# PCB2.net
KiCad netlist of a schematic drawn in EAGLE
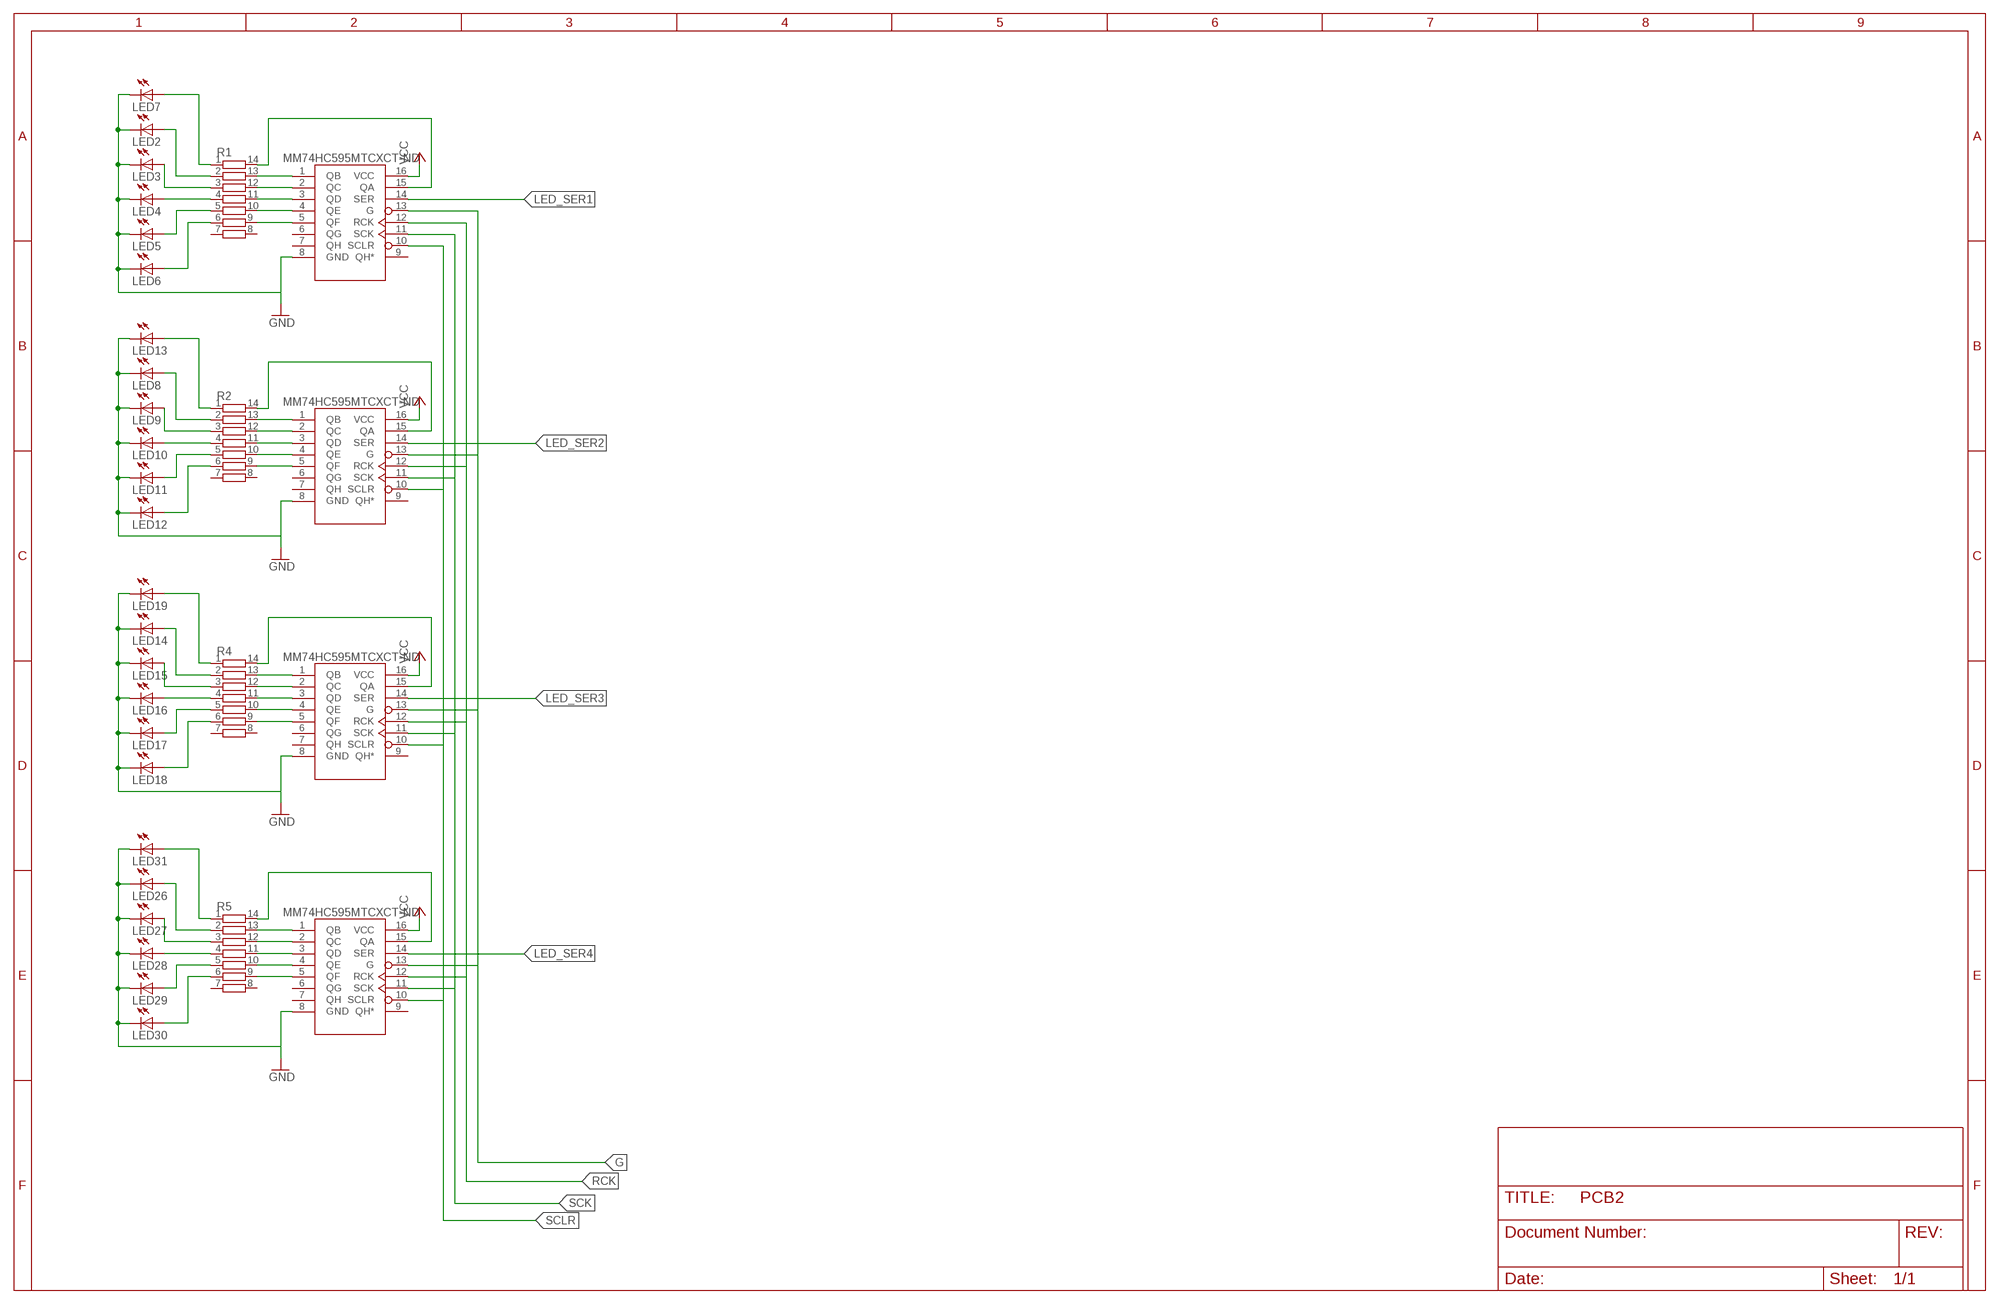
[diagram p0: schematic, sheet 1]

(export (version "E")
  (design (tool "Eeschema 10.0.6"))
  (components
    (comp (ref "LED2")
      (value "LEDSMT1206")
      (footprint "eagle-import:1206")
      (libsource (lib "eagle-import") (part "LEDSMT1206"))
    )
    (comp (ref "LED3")
      (value "LEDSMT1206")
      (footprint "eagle-import:1206")
      (libsource (lib "eagle-import") (part "LEDSMT1206"))
    )
    (comp (ref "LED4")
      (value "LEDSMT1206")
      (footprint "eagle-import:1206")
      (libsource (lib "eagle-import") (part "LEDSMT1206"))
    )
    (comp (ref "LED5")
      (value "LEDSMT1206")
      (footprint "eagle-import:1206")
      (libsource (lib "eagle-import") (part "LEDSMT1206"))
    )
    (comp (ref "LED6")
      (value "LEDSMT1206")
      (footprint "eagle-import:1206")
      (libsource (lib "eagle-import") (part "LEDSMT1206"))
    )
    (comp (ref "LED7")
      (value "LEDSMT1206")
      (footprint "eagle-import:1206")
      (libsource (lib "eagle-import") (part "LEDSMT1206"))
    )
    (comp (ref "LED8")
      (value "LEDSMT1206")
      (footprint "eagle-import:1206")
      (libsource (lib "eagle-import") (part "LEDSMT1206"))
    )
    (comp (ref "LED9")
      (value "LEDSMT1206")
      (footprint "eagle-import:1206")
      (libsource (lib "eagle-import") (part "LEDSMT1206"))
    )
    (comp (ref "LED10")
      (value "LEDSMT1206")
      (footprint "eagle-import:1206")
      (libsource (lib "eagle-import") (part "LEDSMT1206"))
    )
    (comp (ref "LED11")
      (value "LEDSMT1206")
      (footprint "eagle-import:1206")
      (libsource (lib "eagle-import") (part "LEDSMT1206"))
    )
    (comp (ref "LED12")
      (value "LEDSMT1206")
      (footprint "eagle-import:1206")
      (libsource (lib "eagle-import") (part "LEDSMT1206"))
    )
    (comp (ref "LED13")
      (value "LEDSMT1206")
      (footprint "eagle-import:1206")
      (libsource (lib "eagle-import") (part "LEDSMT1206"))
    )
    (comp (ref "LED14")
      (value "LEDSMT1206")
      (footprint "eagle-import:1206")
      (libsource (lib "eagle-import") (part "LEDSMT1206"))
    )
    (comp (ref "LED15")
      (value "LEDSMT1206")
      (footprint "eagle-import:1206")
      (libsource (lib "eagle-import") (part "LEDSMT1206"))
    )
    (comp (ref "LED16")
      (value "LEDSMT1206")
      (footprint "eagle-import:1206")
      (libsource (lib "eagle-import") (part "LEDSMT1206"))
    )
    (comp (ref "LED17")
      (value "LEDSMT1206")
      (footprint "eagle-import:1206")
      (libsource (lib "eagle-import") (part "LEDSMT1206"))
    )
    (comp (ref "LED18")
      (value "LEDSMT1206")
      (footprint "eagle-import:1206")
      (libsource (lib "eagle-import") (part "LEDSMT1206"))
    )
    (comp (ref "LED19")
      (value "LEDSMT1206")
      (footprint "eagle-import:1206")
      (libsource (lib "eagle-import") (part "LEDSMT1206"))
    )
    (comp (ref "LED26")
      (value "LEDSMT1206")
      (footprint "eagle-import:1206")
      (libsource (lib "eagle-import") (part "LEDSMT1206"))
    )
    (comp (ref "LED27")
      (value "LEDSMT1206")
      (footprint "eagle-import:1206")
      (libsource (lib "eagle-import") (part "LEDSMT1206"))
    )
    (comp (ref "LED28")
      (value "LEDSMT1206")
      (footprint "eagle-import:1206")
      (libsource (lib "eagle-import") (part "LEDSMT1206"))
    )
    (comp (ref "LED29")
      (value "LEDSMT1206")
      (footprint "eagle-import:1206")
      (libsource (lib "eagle-import") (part "LEDSMT1206"))
    )
    (comp (ref "LED30")
      (value "LEDSMT1206")
      (footprint "eagle-import:1206")
      (libsource (lib "eagle-import") (part "LEDSMT1206"))
    )
    (comp (ref "LED31")
      (value "LEDSMT1206")
      (footprint "eagle-import:1206")
      (libsource (lib "eagle-import") (part "LEDSMT1206"))
    )
    (comp (ref "R1")
      (value "4814P-T01")
      (footprint "eagle-import:4814P")
      (fields (field (name "MF") "BOURNS, INC.") (field (name "MPN") "4814P-T01-104LF"))
      (libsource (lib "eagle-import") (part "4814P-T01"))
    )
    (comp (ref "R2")
      (value "4814P-T01")
      (footprint "eagle-import:4814P")
      (fields (field (name "MF") "BOURNS, INC.") (field (name "MPN") "4814P-T01-104LF"))
      (libsource (lib "eagle-import") (part "4814P-T01"))
    )
    (comp (ref "R4")
      (value "4814P-T01")
      (footprint "eagle-import:4814P")
      (fields (field (name "MF") "BOURNS, INC.") (field (name "MPN") "4814P-T01-104LF"))
      (libsource (lib "eagle-import") (part "4814P-T01"))
    )
    (comp (ref "R5")
      (value "4814P-T01")
      (footprint "eagle-import:4814P")
      (fields (field (name "MF") "BOURNS, INC.") (field (name "MPN") "4814P-T01-104LF"))
      (libsource (lib "eagle-import") (part "4814P-T01"))
    )
    (comp (ref "U$1")
      (value "MM74HC595TSSOP-LD16")
      (footprint "eagle-import:MM74HC595MTCXCT-ND")
      (libsource (lib "eagle-import") (part "MM74HC595TSSOP-LD16"))
    )
    (comp (ref "U$3")
      (value "MM74HC595TSSOP-LD16")
      (footprint "eagle-import:MM74HC595MTCXCT-ND")
      (libsource (lib "eagle-import") (part "MM74HC595TSSOP-LD16"))
    )
    (comp (ref "U$4")
      (value "MM74HC595TSSOP-LD16")
      (footprint "eagle-import:MM74HC595MTCXCT-ND")
      (libsource (lib "eagle-import") (part "MM74HC595TSSOP-LD16"))
    )
    (comp (ref "U$5")
      (value "MM74HC595TSSOP-LD16")
      (footprint "eagle-import:MM74HC595MTCXCT-ND")
      (libsource (lib "eagle-import") (part "MM74HC595TSSOP-LD16"))
    )
  )
  (nets
    (net (code "1") (name "G") (class "Default")
      (node (ref "U$4") (pin "13") (pinfunction "G_13") (pintype "bidirectional"))
    )
    (net (code "2") (name "GND") (class "Default")
      (node (ref "LED10") (pin "C") (pinfunction "C_C") (pintype "passive"))
      (node (ref "LED11") (pin "C") (pinfunction "C_C") (pintype "passive"))
      (node (ref "LED12") (pin "C") (pinfunction "C_C") (pintype "passive"))
      (node (ref "LED13") (pin "C") (pinfunction "C_C") (pintype "passive"))
      (node (ref "LED14") (pin "C") (pinfunction "C_C") (pintype "passive"))
      (node (ref "LED15") (pin "C") (pinfunction "C_C") (pintype "passive"))
      (node (ref "LED16") (pin "C") (pinfunction "C_C") (pintype "passive"))
      (node (ref "LED17") (pin "C") (pinfunction "C_C") (pintype "passive"))
      (node (ref "LED18") (pin "C") (pinfunction "C_C") (pintype "passive"))
      (node (ref "LED19") (pin "C") (pinfunction "C_C") (pintype "passive"))
      (node (ref "LED2") (pin "C") (pinfunction "C_C") (pintype "passive"))
      (node (ref "LED26") (pin "C") (pinfunction "C_C") (pintype "passive"))
      (node (ref "LED27") (pin "C") (pinfunction "C_C") (pintype "passive"))
      (node (ref "LED28") (pin "C") (pinfunction "C_C") (pintype "passive"))
      (node (ref "LED29") (pin "C") (pinfunction "C_C") (pintype "passive"))
      (node (ref "LED3") (pin "C") (pinfunction "C_C") (pintype "passive"))
      (node (ref "LED30") (pin "C") (pinfunction "C_C") (pintype "passive"))
      (node (ref "LED31") (pin "C") (pinfunction "C_C") (pintype "passive"))
      (node (ref "LED4") (pin "C") (pinfunction "C_C") (pintype "passive"))
      (node (ref "LED5") (pin "C") (pinfunction "C_C") (pintype "passive"))
      (node (ref "LED6") (pin "C") (pinfunction "C_C") (pintype "passive"))
      (node (ref "LED7") (pin "C") (pinfunction "C_C") (pintype "passive"))
      (node (ref "LED8") (pin "C") (pinfunction "C_C") (pintype "passive"))
      (node (ref "LED9") (pin "C") (pinfunction "C_C") (pintype "passive"))
      (node (ref "U$1") (pin "8") (pinfunction "GND_8") (pintype "bidirectional"))
      (node (ref "U$3") (pin "8") (pinfunction "GND_8") (pintype "bidirectional"))
      (node (ref "U$4") (pin "8") (pinfunction "GND_8") (pintype "bidirectional"))
      (node (ref "U$5") (pin "8") (pinfunction "GND_8") (pintype "bidirectional"))
    )
    (net (code "3") (name "LED_SER1") (class "Default")
      (node (ref "U$4") (pin "14") (pinfunction "SER_14") (pintype "bidirectional"))
    )
    (net (code "4") (name "LED_SER2") (class "Default")
      (node (ref "U$1") (pin "14") (pinfunction "SER_14") (pintype "bidirectional"))
    )
    (net (code "5") (name "LED_SER3") (class "Default")
      (node (ref "U$3") (pin "14") (pinfunction "SER_14") (pintype "bidirectional"))
    )
    (net (code "6") (name "LED_SER4") (class "Default")
      (node (ref "U$5") (pin "14") (pinfunction "SER_14") (pintype "bidirectional"))
    )
    (net (code "7") (name "Net-(LED2-PadA)") (class "Default")
      (node (ref "LED2") (pin "A") (pinfunction "A_A") (pintype "passive"))
      (node (ref "R1") (pin "2") (pinfunction "2_2") (pintype "passive"))
    )
    (net (code "8") (name "Net-(LED3-PadA)") (class "Default")
      (node (ref "LED3") (pin "A") (pinfunction "A_A") (pintype "passive"))
      (node (ref "R1") (pin "3") (pinfunction "3_3") (pintype "passive"))
    )
    (net (code "9") (name "Net-(LED4-PadA)") (class "Default")
      (node (ref "LED4") (pin "A") (pinfunction "A_A") (pintype "passive"))
      (node (ref "R1") (pin "4") (pinfunction "4_4") (pintype "passive"))
    )
    (net (code "10") (name "Net-(LED5-PadA)") (class "Default")
      (node (ref "LED5") (pin "A") (pinfunction "A_A") (pintype "passive"))
      (node (ref "R1") (pin "5") (pinfunction "5_5") (pintype "passive"))
    )
    (net (code "11") (name "Net-(LED6-PadA)") (class "Default")
      (node (ref "LED6") (pin "A") (pinfunction "A_A") (pintype "passive"))
      (node (ref "R1") (pin "6") (pinfunction "6_6") (pintype "passive"))
    )
    (net (code "12") (name "Net-(LED7-PadA)") (class "Default")
      (node (ref "LED7") (pin "A") (pinfunction "A_A") (pintype "passive"))
      (node (ref "R1") (pin "1") (pinfunction "1_1") (pintype "passive"))
    )
    (net (code "13") (name "Net-(LED8-PadA)") (class "Default")
      (node (ref "LED8") (pin "A") (pinfunction "A_A") (pintype "passive"))
      (node (ref "R2") (pin "2") (pinfunction "2_2") (pintype "passive"))
    )
    (net (code "14") (name "Net-(LED9-PadA)") (class "Default")
      (node (ref "LED9") (pin "A") (pinfunction "A_A") (pintype "passive"))
      (node (ref "R2") (pin "3") (pinfunction "3_3") (pintype "passive"))
    )
    (net (code "15") (name "Net-(LED10-PadA)") (class "Default")
      (node (ref "LED10") (pin "A") (pinfunction "A_A") (pintype "passive"))
      (node (ref "R2") (pin "4") (pinfunction "4_4") (pintype "passive"))
    )
    (net (code "16") (name "Net-(LED11-PadA)") (class "Default")
      (node (ref "LED11") (pin "A") (pinfunction "A_A") (pintype "passive"))
      (node (ref "R2") (pin "5") (pinfunction "5_5") (pintype "passive"))
    )
    (net (code "17") (name "Net-(LED12-PadA)") (class "Default")
      (node (ref "LED12") (pin "A") (pinfunction "A_A") (pintype "passive"))
      (node (ref "R2") (pin "6") (pinfunction "6_6") (pintype "passive"))
    )
    (net (code "18") (name "Net-(LED13-PadA)") (class "Default")
      (node (ref "LED13") (pin "A") (pinfunction "A_A") (pintype "passive"))
      (node (ref "R2") (pin "1") (pinfunction "1_1") (pintype "passive"))
    )
    (net (code "19") (name "Net-(LED14-PadA)") (class "Default")
      (node (ref "LED14") (pin "A") (pinfunction "A_A") (pintype "passive"))
      (node (ref "R4") (pin "2") (pinfunction "2_2") (pintype "passive"))
    )
    (net (code "20") (name "Net-(LED15-PadA)") (class "Default")
      (node (ref "LED15") (pin "A") (pinfunction "A_A") (pintype "passive"))
      (node (ref "R4") (pin "3") (pinfunction "3_3") (pintype "passive"))
    )
    (net (code "21") (name "Net-(LED16-PadA)") (class "Default")
      (node (ref "LED16") (pin "A") (pinfunction "A_A") (pintype "passive"))
      (node (ref "R4") (pin "4") (pinfunction "4_4") (pintype "passive"))
    )
    (net (code "22") (name "Net-(LED17-PadA)") (class "Default")
      (node (ref "LED17") (pin "A") (pinfunction "A_A") (pintype "passive"))
      (node (ref "R4") (pin "5") (pinfunction "5_5") (pintype "passive"))
    )
    (net (code "23") (name "Net-(LED18-PadA)") (class "Default")
      (node (ref "LED18") (pin "A") (pinfunction "A_A") (pintype "passive"))
      (node (ref "R4") (pin "6") (pinfunction "6_6") (pintype "passive"))
    )
    (net (code "24") (name "Net-(LED19-PadA)") (class "Default")
      (node (ref "LED19") (pin "A") (pinfunction "A_A") (pintype "passive"))
      (node (ref "R4") (pin "1") (pinfunction "1_1") (pintype "passive"))
    )
    (net (code "25") (name "Net-(LED26-PadA)") (class "Default")
      (node (ref "LED26") (pin "A") (pinfunction "A_A") (pintype "passive"))
      (node (ref "R5") (pin "2") (pinfunction "2_2") (pintype "passive"))
    )
    (net (code "26") (name "Net-(LED27-PadA)") (class "Default")
      (node (ref "LED27") (pin "A") (pinfunction "A_A") (pintype "passive"))
      (node (ref "R5") (pin "3") (pinfunction "3_3") (pintype "passive"))
    )
    (net (code "27") (name "Net-(LED28-PadA)") (class "Default")
      (node (ref "LED28") (pin "A") (pinfunction "A_A") (pintype "passive"))
      (node (ref "R5") (pin "4") (pinfunction "4_4") (pintype "passive"))
    )
    (net (code "28") (name "Net-(LED29-PadA)") (class "Default")
      (node (ref "LED29") (pin "A") (pinfunction "A_A") (pintype "passive"))
      (node (ref "R5") (pin "5") (pinfunction "5_5") (pintype "passive"))
    )
    (net (code "29") (name "Net-(LED30-PadA)") (class "Default")
      (node (ref "LED30") (pin "A") (pinfunction "A_A") (pintype "passive"))
      (node (ref "R5") (pin "6") (pinfunction "6_6") (pintype "passive"))
    )
    (net (code "30") (name "Net-(LED31-PadA)") (class "Default")
      (node (ref "LED31") (pin "A") (pinfunction "A_A") (pintype "passive"))
      (node (ref "R5") (pin "1") (pinfunction "1_1") (pintype "passive"))
    )
    (net (code "31") (name "Net-(U$1-QA)") (class "Default")
      (node (ref "R2") (pin "14") (pinfunction "14_14") (pintype "passive"))
      (node (ref "U$1") (pin "15") (pinfunction "QA_15") (pintype "bidirectional"))
    )
    (net (code "32") (name "Net-(U$1-QB)") (class "Default")
      (node (ref "R2") (pin "13") (pinfunction "13_13") (pintype "passive"))
      (node (ref "U$1") (pin "1") (pinfunction "QB_1") (pintype "bidirectional"))
    )
    (net (code "33") (name "Net-(U$1-QC)") (class "Default")
      (node (ref "R2") (pin "12") (pinfunction "12_12") (pintype "passive"))
      (node (ref "U$1") (pin "2") (pinfunction "QC_2") (pintype "bidirectional"))
    )
    (net (code "34") (name "Net-(U$1-QD)") (class "Default")
      (node (ref "R2") (pin "11") (pinfunction "11_11") (pintype "passive"))
      (node (ref "U$1") (pin "3") (pinfunction "QD_3") (pintype "bidirectional"))
    )
    (net (code "35") (name "Net-(U$1-QE)") (class "Default")
      (node (ref "R2") (pin "10") (pinfunction "10_10") (pintype "passive"))
      (node (ref "U$1") (pin "4") (pinfunction "QE_4") (pintype "bidirectional"))
    )
    (net (code "36") (name "Net-(U$1-QF)") (class "Default")
      (node (ref "R2") (pin "9") (pinfunction "9_9") (pintype "passive"))
      (node (ref "U$1") (pin "5") (pinfunction "QF_5") (pintype "bidirectional"))
    )
    (net (code "37") (name "Net-(U$3-QA)") (class "Default")
      (node (ref "R4") (pin "14") (pinfunction "14_14") (pintype "passive"))
      (node (ref "U$3") (pin "15") (pinfunction "QA_15") (pintype "bidirectional"))
    )
    (net (code "38") (name "Net-(U$3-QB)") (class "Default")
      (node (ref "R4") (pin "13") (pinfunction "13_13") (pintype "passive"))
      (node (ref "U$3") (pin "1") (pinfunction "QB_1") (pintype "bidirectional"))
    )
    (net (code "39") (name "Net-(U$3-QC)") (class "Default")
      (node (ref "R4") (pin "12") (pinfunction "12_12") (pintype "passive"))
      (node (ref "U$3") (pin "2") (pinfunction "QC_2") (pintype "bidirectional"))
    )
    (net (code "40") (name "Net-(U$3-QD)") (class "Default")
      (node (ref "R4") (pin "11") (pinfunction "11_11") (pintype "passive"))
      (node (ref "U$3") (pin "3") (pinfunction "QD_3") (pintype "bidirectional"))
    )
    (net (code "41") (name "Net-(U$3-QE)") (class "Default")
      (node (ref "R4") (pin "10") (pinfunction "10_10") (pintype "passive"))
      (node (ref "U$3") (pin "4") (pinfunction "QE_4") (pintype "bidirectional"))
    )
    (net (code "42") (name "Net-(U$3-QF)") (class "Default")
      (node (ref "R4") (pin "9") (pinfunction "9_9") (pintype "passive"))
      (node (ref "U$3") (pin "5") (pinfunction "QF_5") (pintype "bidirectional"))
    )
    (net (code "43") (name "Net-(U$4-QA)") (class "Default")
      (node (ref "R1") (pin "14") (pinfunction "14_14") (pintype "passive"))
      (node (ref "U$4") (pin "15") (pinfunction "QA_15") (pintype "bidirectional"))
    )
    (net (code "44") (name "Net-(U$4-QB)") (class "Default")
      (node (ref "R1") (pin "13") (pinfunction "13_13") (pintype "passive"))
      (node (ref "U$4") (pin "1") (pinfunction "QB_1") (pintype "bidirectional"))
    )
    (net (code "45") (name "Net-(U$4-QC)") (class "Default")
      (node (ref "R1") (pin "12") (pinfunction "12_12") (pintype "passive"))
      (node (ref "U$4") (pin "2") (pinfunction "QC_2") (pintype "bidirectional"))
    )
    (net (code "46") (name "Net-(U$4-QD)") (class "Default")
      (node (ref "R1") (pin "11") (pinfunction "11_11") (pintype "passive"))
      (node (ref "U$4") (pin "3") (pinfunction "QD_3") (pintype "bidirectional"))
    )
    (net (code "47") (name "Net-(U$4-QE)") (class "Default")
      (node (ref "R1") (pin "10") (pinfunction "10_10") (pintype "passive"))
      (node (ref "U$4") (pin "4") (pinfunction "QE_4") (pintype "bidirectional"))
    )
    (net (code "48") (name "Net-(U$4-QF)") (class "Default")
      (node (ref "R1") (pin "9") (pinfunction "9_9") (pintype "passive"))
      (node (ref "U$4") (pin "5") (pinfunction "QF_5") (pintype "bidirectional"))
    )
    (net (code "49") (name "Net-(U$5-QA)") (class "Default")
      (node (ref "R5") (pin "14") (pinfunction "14_14") (pintype "passive"))
      (node (ref "U$5") (pin "15") (pinfunction "QA_15") (pintype "bidirectional"))
    )
    (net (code "50") (name "Net-(U$5-QB)") (class "Default")
      (node (ref "R5") (pin "13") (pinfunction "13_13") (pintype "passive"))
      (node (ref "U$5") (pin "1") (pinfunction "QB_1") (pintype "bidirectional"))
    )
    (net (code "51") (name "Net-(U$5-QC)") (class "Default")
      (node (ref "R5") (pin "12") (pinfunction "12_12") (pintype "passive"))
      (node (ref "U$5") (pin "2") (pinfunction "QC_2") (pintype "bidirectional"))
    )
    (net (code "52") (name "Net-(U$5-QD)") (class "Default")
      (node (ref "R5") (pin "11") (pinfunction "11_11") (pintype "passive"))
      (node (ref "U$5") (pin "3") (pinfunction "QD_3") (pintype "bidirectional"))
    )
    (net (code "53") (name "Net-(U$5-QE)") (class "Default")
      (node (ref "R5") (pin "10") (pinfunction "10_10") (pintype "passive"))
      (node (ref "U$5") (pin "4") (pinfunction "QE_4") (pintype "bidirectional"))
    )
    (net (code "54") (name "Net-(U$5-QF)") (class "Default")
      (node (ref "R5") (pin "9") (pinfunction "9_9") (pintype "passive"))
      (node (ref "U$5") (pin "5") (pinfunction "QF_5") (pintype "bidirectional"))
    )
    (net (code "55") (name "RCK") (class "Default")
      (node (ref "U$4") (pin "12") (pinfunction "RCK_12") (pintype "bidirectional"))
    )
    (net (code "56") (name "SCK") (class "Default")
      (node (ref "U$4") (pin "11") (pinfunction "SCK_11") (pintype "bidirectional"))
    )
    (net (code "57") (name "SCLR") (class "Default")
      (node (ref "U$1") (pin "10") (pinfunction "SCLR_10") (pintype "bidirectional"))
      (node (ref "U$3") (pin "10") (pinfunction "SCLR_10") (pintype "bidirectional"))
      (node (ref "U$4") (pin "10") (pinfunction "SCLR_10") (pintype "bidirectional"))
      (node (ref "U$5") (pin "10") (pinfunction "SCLR_10") (pintype "bidirectional"))
    )
    (net (code "58") (name "VCC") (class "Default")
      (node (ref "U$1") (pin "16") (pinfunction "VCC_16") (pintype "bidirectional"))
      (node (ref "U$3") (pin "16") (pinfunction "VCC_16") (pintype "bidirectional"))
      (node (ref "U$4") (pin "16") (pinfunction "VCC_16") (pintype "bidirectional"))
      (node (ref "U$5") (pin "16") (pinfunction "VCC_16") (pintype "bidirectional"))
    )
    (net (code "59") (name "unconnected-(R1-Pad7)") (class "Default")
      (node (ref "R1") (pin "7") (pinfunction "7_7") (pintype "passive"))
    )
    (net (code "60") (name "unconnected-(R1-Pad8)") (class "Default")
      (node (ref "R1") (pin "8") (pinfunction "8_8") (pintype "passive"))
    )
    (net (code "61") (name "unconnected-(R2-Pad7)") (class "Default")
      (node (ref "R2") (pin "7") (pinfunction "7_7") (pintype "passive"))
    )
    (net (code "62") (name "unconnected-(R2-Pad8)") (class "Default")
      (node (ref "R2") (pin "8") (pinfunction "8_8") (pintype "passive"))
    )
    (net (code "63") (name "unconnected-(R4-Pad7)") (class "Default")
      (node (ref "R4") (pin "7") (pinfunction "7_7") (pintype "passive"))
    )
    (net (code "64") (name "unconnected-(R4-Pad8)") (class "Default")
      (node (ref "R4") (pin "8") (pinfunction "8_8") (pintype "passive"))
    )
    (net (code "65") (name "unconnected-(R5-Pad7)") (class "Default")
      (node (ref "R5") (pin "7") (pinfunction "7_7") (pintype "passive"))
    )
    (net (code "66") (name "unconnected-(R5-Pad8)") (class "Default")
      (node (ref "R5") (pin "8") (pinfunction "8_8") (pintype "passive"))
    )
    (net (code "67") (name "unconnected-(U$1-G-Pad13)") (class "Default")
      (node (ref "U$1") (pin "13") (pinfunction "G_13") (pintype "bidirectional"))
    )
    (net (code "68") (name "unconnected-(U$1-QG-Pad6)") (class "Default")
      (node (ref "U$1") (pin "6") (pinfunction "QG_6") (pintype "bidirectional"))
    )
    (net (code "69") (name "unconnected-(U$1-QH*-Pad9)") (class "Default")
      (node (ref "U$1") (pin "9") (pinfunction "QH*_9") (pintype "bidirectional"))
    )
    (net (code "70") (name "unconnected-(U$1-QH-Pad7)") (class "Default")
      (node (ref "U$1") (pin "7") (pinfunction "QH_7") (pintype "bidirectional"))
    )
    (net (code "71") (name "unconnected-(U$1-RCK-Pad12)") (class "Default")
      (node (ref "U$1") (pin "12") (pinfunction "RCK_12") (pintype "bidirectional"))
    )
    (net (code "72") (name "unconnected-(U$1-SCK-Pad11)") (class "Default")
      (node (ref "U$1") (pin "11") (pinfunction "SCK_11") (pintype "bidirectional"))
    )
    (net (code "73") (name "unconnected-(U$3-G-Pad13)") (class "Default")
      (node (ref "U$3") (pin "13") (pinfunction "G_13") (pintype "bidirectional"))
    )
    (net (code "74") (name "unconnected-(U$3-QG-Pad6)") (class "Default")
      (node (ref "U$3") (pin "6") (pinfunction "QG_6") (pintype "bidirectional"))
    )
    (net (code "75") (name "unconnected-(U$3-QH*-Pad9)") (class "Default")
      (node (ref "U$3") (pin "9") (pinfunction "QH*_9") (pintype "bidirectional"))
    )
    (net (code "76") (name "unconnected-(U$3-QH-Pad7)") (class "Default")
      (node (ref "U$3") (pin "7") (pinfunction "QH_7") (pintype "bidirectional"))
    )
    (net (code "77") (name "unconnected-(U$3-RCK-Pad12)") (class "Default")
      (node (ref "U$3") (pin "12") (pinfunction "RCK_12") (pintype "bidirectional"))
    )
    (net (code "78") (name "unconnected-(U$3-SCK-Pad11)") (class "Default")
      (node (ref "U$3") (pin "11") (pinfunction "SCK_11") (pintype "bidirectional"))
    )
    (net (code "79") (name "unconnected-(U$4-QG-Pad6)") (class "Default")
      (node (ref "U$4") (pin "6") (pinfunction "QG_6") (pintype "bidirectional"))
    )
    (net (code "80") (name "unconnected-(U$4-QH*-Pad9)") (class "Default")
      (node (ref "U$4") (pin "9") (pinfunction "QH*_9") (pintype "bidirectional"))
    )
    (net (code "81") (name "unconnected-(U$4-QH-Pad7)") (class "Default")
      (node (ref "U$4") (pin "7") (pinfunction "QH_7") (pintype "bidirectional"))
    )
    (net (code "82") (name "unconnected-(U$5-G-Pad13)") (class "Default")
      (node (ref "U$5") (pin "13") (pinfunction "G_13") (pintype "bidirectional"))
    )
    (net (code "83") (name "unconnected-(U$5-QG-Pad6)") (class "Default")
      (node (ref "U$5") (pin "6") (pinfunction "QG_6") (pintype "bidirectional"))
    )
    (net (code "84") (name "unconnected-(U$5-QH*-Pad9)") (class "Default")
      (node (ref "U$5") (pin "9") (pinfunction "QH*_9") (pintype "bidirectional"))
    )
    (net (code "85") (name "unconnected-(U$5-QH-Pad7)") (class "Default")
      (node (ref "U$5") (pin "7") (pinfunction "QH_7") (pintype "bidirectional"))
    )
    (net (code "86") (name "unconnected-(U$5-RCK-Pad12)") (class "Default")
      (node (ref "U$5") (pin "12") (pinfunction "RCK_12") (pintype "bidirectional"))
    )
    (net (code "87") (name "unconnected-(U$5-SCK-Pad11)") (class "Default")
      (node (ref "U$5") (pin "11") (pinfunction "SCK_11") (pintype "bidirectional"))
    )
  )
)
